# PIC_backpack.net
KiCad netlist of a schematic drawn in EAGLE
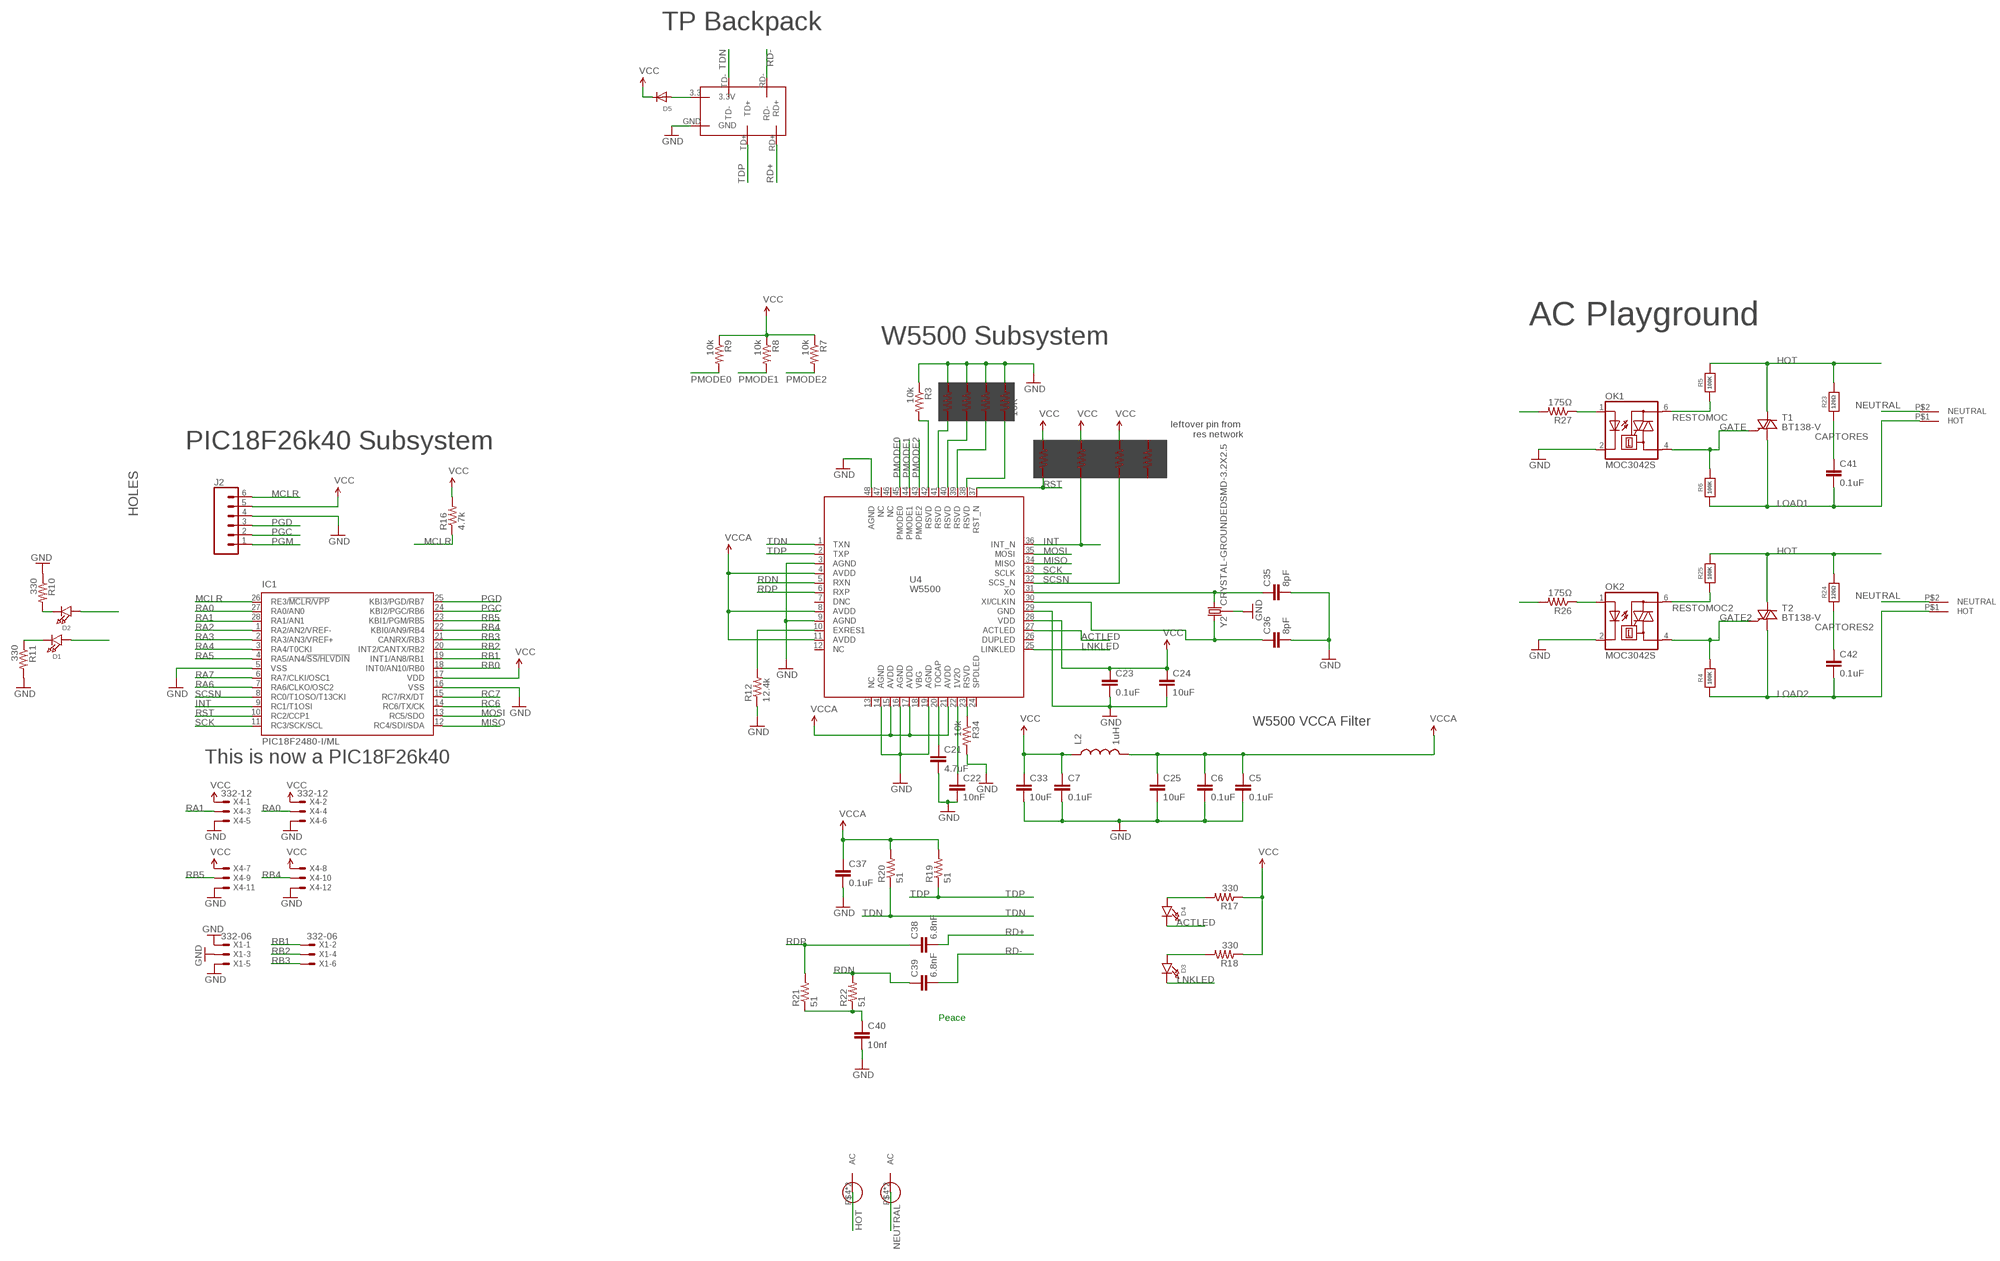
[diagram p0: schematic, sheet 1]

(export (version "E")
  (design (tool "Eeschema 10.0.6"))
  (components
    (comp (ref "C5")
      (value "0.1uF")
      (footprint "eagle-import:0603-CAP")
      (libsource (lib "eagle-import") (part "SparkFun-Passives_CAP0603-CAP"))
    )
    (comp (ref "C6")
      (value "0.1uF")
      (footprint "eagle-import:0603-CAP")
      (libsource (lib "eagle-import") (part "SparkFun-Passives_CAP0603-CAP"))
    )
    (comp (ref "C7")
      (value "0.1uF")
      (footprint "eagle-import:0603-CAP")
      (libsource (lib "eagle-import") (part "SparkFun-Passives_CAP0603-CAP"))
    )
    (comp (ref "C21")
      (value "4.7uF")
      (footprint "eagle-import:0603-CAP")
      (libsource (lib "eagle-import") (part "SparkFun-Passives_CAP0603-CAP"))
    )
    (comp (ref "C22")
      (value "10nF")
      (footprint "eagle-import:0603-CAP")
      (libsource (lib "eagle-import") (part "SparkFun-Passives_CAP0603-CAP"))
    )
    (comp (ref "C23")
      (value "0.1uF")
      (footprint "eagle-import:0603-CAP")
      (libsource (lib "eagle-import") (part "SparkFun-Passives_CAP0603-CAP"))
    )
    (comp (ref "C24")
      (value "10uF")
      (footprint "eagle-import:0603-CAP")
      (libsource (lib "eagle-import") (part "SparkFun-Passives_CAP0603-CAP"))
    )
    (comp (ref "C25")
      (value "10uF")
      (footprint "eagle-import:0603-CAP")
      (libsource (lib "eagle-import") (part "SparkFun-Passives_CAP0603-CAP"))
    )
    (comp (ref "C33")
      (value "10uF")
      (footprint "eagle-import:0603-CAP")
      (libsource (lib "eagle-import") (part "SparkFun-Passives_CAP0603-CAP"))
    )
    (comp (ref "C35")
      (value "8pF")
      (footprint "eagle-import:0603-CAP")
      (libsource (lib "eagle-import") (part "SparkFun-Passives_CAP0603-CAP"))
    )
    (comp (ref "C36")
      (value "8pF")
      (footprint "eagle-import:0603-CAP")
      (libsource (lib "eagle-import") (part "SparkFun-Passives_CAP0603-CAP"))
    )
    (comp (ref "C37")
      (value "0.1uF")
      (footprint "eagle-import:0603-CAP")
      (libsource (lib "eagle-import") (part "SparkFun-Passives_CAP0603-CAP"))
    )
    (comp (ref "C38")
      (value "6.8nF")
      (footprint "eagle-import:0603-CAP")
      (libsource (lib "eagle-import") (part "SparkFun-Passives_CAP0603-CAP"))
    )
    (comp (ref "C39")
      (value "6.8nF")
      (footprint "eagle-import:0603-CAP")
      (libsource (lib "eagle-import") (part "SparkFun-Passives_CAP0603-CAP"))
    )
    (comp (ref "C40")
      (value "10nf")
      (footprint "eagle-import:0603-CAP")
      (libsource (lib "eagle-import") (part "SparkFun-Passives_CAP0603-CAP"))
    )
    (comp (ref "C41")
      (value "0.1uF")
      (footprint "eagle-import:1210")
      (libsource (lib "eagle-import") (part "CAP1210"))
    )
    (comp (ref "C42")
      (value "0.1uF")
      (footprint "eagle-import:1210")
      (libsource (lib "eagle-import") (part "CAP1210"))
    )
    (comp (ref "D1")
      (value "LED0603_NOOUTLINE")
      (footprint "eagle-import:CHIPLED_0603_NOOUTLINE")
      (libsource (lib "eagle-import") (part "LED0603_NOOUTLINE"))
    )
    (comp (ref "D2")
      (value "LED0603_NOOUTLINE")
      (footprint "eagle-import:CHIPLED_0603_NOOUTLINE")
      (libsource (lib "eagle-import") (part "LED0603_NOOUTLINE"))
    )
    (comp (ref "D3")
      (value "LED0603_NOOUTLINE")
      (footprint "eagle-import:CHIPLED_0603_NOOUTLINE")
      (libsource (lib "eagle-import") (part "LED0603_NOOUTLINE"))
    )
    (comp (ref "D4")
      (value "LED0603_NOOUTLINE")
      (footprint "eagle-import:CHIPLED_0603_NOOUTLINE")
      (libsource (lib "eagle-import") (part "LED0603_NOOUTLINE"))
    )
    (comp (ref "D5")
      (value "DIODESOD-123")
      (footprint "eagle-import:SOD-123")
      (libsource (lib "eagle-import") (part "DIODESOD-123"))
    )
    (comp (ref "IC1")
      (value "PIC18F2480-I/ML")
      (footprint "eagle-import:QFN28-ML_6X6MM")
      (fields (field (name "MF") "MICROCHIP"))
      (libsource (lib "eagle-import") (part "PIC18F280-I/ML4"))
    )
    (comp (ref "J2")
      (value "CONN_06NO_SILK_FEMALE_PTH")
      (footprint "eagle-import:1X06_NO_SILK")
      (libsource (lib "eagle-import") (part "CONN_06NO_SILK_FEMALE_PTH"))
    )
    (comp (ref "L2")
      (value "1uH")
      (footprint "eagle-import:0603")
      (libsource (lib "eagle-import") (part "INDUCTOR0603"))
    )
    (comp (ref "OK1")
      (value "MOC3042S")
      (footprint "eagle-import:DIL6-SMD")
      (fields (field (name "MF") "FAIRCHILD SEMICONDUCTOR") (field (name "MPN") "MOC3042SM"))
      (libsource (lib "eagle-import") (part "MOC30S42"))
    )
    (comp (ref "OK2")
      (value "MOC3042S")
      (footprint "eagle-import:DIL6-SMD")
      (fields (field (name "MF") "FAIRCHILD SEMICONDUCTOR") (field (name "MPN") "MOC3042SM"))
      (libsource (lib "eagle-import") (part "MOC30S42"))
    )
    (comp (ref "R1")
      (value "10K")
      (footprint "eagle-import:RESPACK_4X0603")
      (libsource (lib "eagle-import") (part "RESISTOR_4PACK_US"))
    )
    (comp (ref "R2")
      (value "10K")
      (footprint "eagle-import:RESPACK_4X0603")
      (libsource (lib "eagle-import") (part "RESISTOR_4PACK_US"))
    )
    (comp (ref "R3")
      (value "10k")
      (footprint "eagle-import:0603-RES")
      (libsource (lib "eagle-import") (part "RESISTOR0603-RES"))
    )
    (comp (ref "R4")
      (value "100K")
      (footprint "eagle-import:0805_10MGAP")
      (libsource (lib "eagle-import") (part "RESISTOR0805_10MGAP"))
    )
    (comp (ref "R5")
      (value "100K")
      (footprint "eagle-import:0805_10MGAP")
      (libsource (lib "eagle-import") (part "RESISTOR0805_10MGAP"))
    )
    (comp (ref "R6")
      (value "100K")
      (footprint "eagle-import:0805_10MGAP")
      (libsource (lib "eagle-import") (part "RESISTOR0805_10MGAP"))
    )
    (comp (ref "R7")
      (value "10k")
      (footprint "eagle-import:0603-RES")
      (libsource (lib "eagle-import") (part "RESISTOR0603-RES"))
    )
    (comp (ref "R8")
      (value "10k")
      (footprint "eagle-import:0603-RES")
      (libsource (lib "eagle-import") (part "RESISTOR0603-RES"))
    )
    (comp (ref "R9")
      (value "10k")
      (footprint "eagle-import:0603-RES")
      (libsource (lib "eagle-import") (part "RESISTOR0603-RES"))
    )
    (comp (ref "R10")
      (value "330")
      (footprint "eagle-import:0603-RES")
      (libsource (lib "eagle-import") (part "RESISTOR0603-RES"))
    )
    (comp (ref "R11")
      (value "330")
      (footprint "eagle-import:0603-RES")
      (libsource (lib "eagle-import") (part "RESISTOR0603-RES"))
    )
    (comp (ref "R12")
      (value "12.4k")
      (footprint "eagle-import:0603-RES")
      (libsource (lib "eagle-import") (part "RESISTOR0603-RES"))
    )
    (comp (ref "R16")
      (value "4.7k")
      (footprint "eagle-import:0603-RES")
      (libsource (lib "eagle-import") (part "RESISTOR0603-RES"))
    )
    (comp (ref "R17")
      (value "330")
      (footprint "eagle-import:0603-RES")
      (libsource (lib "eagle-import") (part "RESISTOR0603-RES"))
    )
    (comp (ref "R18")
      (value "330")
      (footprint "eagle-import:0603-RES")
      (libsource (lib "eagle-import") (part "RESISTOR0603-RES"))
    )
    (comp (ref "R19")
      (value "51")
      (footprint "eagle-import:0603-RES")
      (libsource (lib "eagle-import") (part "RESISTOR0603-RES"))
    )
    (comp (ref "R20")
      (value "51")
      (footprint "eagle-import:0603-RES")
      (libsource (lib "eagle-import") (part "RESISTOR0603-RES"))
    )
    (comp (ref "R21")
      (value "51")
      (footprint "eagle-import:0603-RES")
      (libsource (lib "eagle-import") (part "RESISTOR0603-RES"))
    )
    (comp (ref "R22")
      (value "51")
      (footprint "eagle-import:0603-RES")
      (libsource (lib "eagle-import") (part "RESISTOR0603-RES"))
    )
    (comp (ref "R23")
      (value "120Ω")
      (footprint "eagle-import:0805_10MGAP")
      (libsource (lib "eagle-import") (part "RESISTOR0805_10MGAP"))
    )
    (comp (ref "R24")
      (value "120Ω")
      (footprint "eagle-import:0805_10MGAP")
      (libsource (lib "eagle-import") (part "RESISTOR0805_10MGAP"))
    )
    (comp (ref "R25")
      (value "100K")
      (footprint "eagle-import:0805_10MGAP")
      (libsource (lib "eagle-import") (part "RESISTOR0805_10MGAP"))
    )
    (comp (ref "R26")
      (value "175Ω")
      (footprint "eagle-import:0603-RES")
      (libsource (lib "eagle-import") (part "RESISTOR0603-RES"))
    )
    (comp (ref "R27")
      (value "175Ω")
      (footprint "eagle-import:0603-RES")
      (libsource (lib "eagle-import") (part "RESISTOR0603-RES"))
    )
    (comp (ref "R34")
      (value "10k")
      (footprint "eagle-import:0603-RES")
      (libsource (lib "eagle-import") (part "RESISTOR0603-RES"))
    )
    (comp (ref "T1")
      (value "BT138-V")
      (footprint "eagle-import:TO220BV")
      (libsource (lib "eagle-import") (part "BT138-V"))
    )
    (comp (ref "T2")
      (value "BT138-V")
      (footprint "eagle-import:TO220BV")
      (libsource (lib "eagle-import") (part "BT138-V"))
    )
    (comp (ref "U$1")
      (value "TPLINK_BACKPACK")
      (footprint "eagle-import:BACKPACK_WITH_PROTO")
      (libsource (lib "eagle-import") (part "TPLINK_BACKPACK"))
    )
    (comp (ref "U$2")
      (value "AC_BLADE")
      (footprint "eagle-import:AC_BLADE")
      (libsource (lib "eagle-import") (part "AC_BLADE"))
    )
    (comp (ref "U$3")
      (value "AC_BLADE")
      (footprint "eagle-import:AC_BLADE")
      (libsource (lib "eagle-import") (part "AC_BLADE"))
    )
    (comp (ref "U$4")
      (value "AC_TERMINAL")
      (footprint "eagle-import:AC_TERMINAL")
      (libsource (lib "eagle-import") (part "AC_TERMINAL"))
    )
    (comp (ref "U$5")
      (value "AC_TERMINAL")
      (footprint "eagle-import:AC_TERMINAL")
      (libsource (lib "eagle-import") (part "AC_TERMINAL"))
    )
    (comp (ref "U4")
      (value "W5500")
      (footprint "eagle-import:W5500")
      (libsource (lib "eagle-import") (part "W5500"))
    )
    (comp (ref "X1")
      (value "332-06")
      (footprint "eagle-import:332-06")
      (libsource (lib "eagle-import") (part "332-06"))
    )
    (comp (ref "X4")
      (value "332-12")
      (footprint "eagle-import:332-12")
      (libsource (lib "eagle-import") (part "332-12"))
    )
    (comp (ref "Y2")
      (value "CRYSTAL-GROUNDEDSMD-3.2X2.5")
      (footprint "eagle-import:CRYSTAL-SMD-3.2X2.5MM")
      (libsource (lib "eagle-import") (part "CRYSTAL-GROUNDEDSMD-3.2X2.5"))
    )
  )
  (nets
    (net (code "1") (name "/ACTLED") (class "Default")
      (node (ref "D4") (pin "C") (pinfunction "C_C") (pintype "passive"))
      (node (ref "U4") (pin "27") (pinfunction "ACTLED_27") (pintype "passive"))
    )
    (net (code "2") (name "/CAPTORES") (class "Default")
      (node (ref "C41") (pin "1") (pinfunction "1_1") (pintype "passive"))
      (node (ref "R23") (pin "1") (pinfunction "1_1") (pintype "passive"))
    )
    (net (code "3") (name "/CAPTORES2") (class "Default")
      (node (ref "C42") (pin "1") (pinfunction "1_1") (pintype "passive"))
      (node (ref "R24") (pin "1") (pinfunction "1_1") (pintype "passive"))
    )
    (net (code "4") (name "/GATE") (class "Default")
      (node (ref "OK1") (pin "4") (pinfunction "A1_4") (pintype "passive"))
      (node (ref "R6") (pin "2") (pinfunction "2_2") (pintype "passive"))
      (node (ref "T1") (pin "G") (pinfunction "G_G") (pintype "passive"))
    )
    (net (code "5") (name "/GATE2") (class "Default")
      (node (ref "OK2") (pin "4") (pinfunction "A1_4") (pintype "passive"))
      (node (ref "R4") (pin "2") (pinfunction "2_2") (pintype "passive"))
      (node (ref "T2") (pin "G") (pinfunction "G_G") (pintype "passive"))
    )
    (net (code "6") (name "/HOT") (class "Default")
      (node (ref "R23") (pin "2") (pinfunction "2_2") (pintype "passive"))
      (node (ref "R24") (pin "2") (pinfunction "2_2") (pintype "passive"))
      (node (ref "R25") (pin "2") (pinfunction "2_2") (pintype "passive"))
      (node (ref "R5") (pin "2") (pinfunction "2_2") (pintype "passive"))
      (node (ref "T1") (pin "T2") (pinfunction "A2_T2") (pintype "passive"))
      (node (ref "T2") (pin "T2") (pinfunction "A2_T2") (pintype "passive"))
      (node (ref "U$2") (pin "P$4") (pinfunction "AC_P$4") (pintype "bidirectional"))
      (node (ref "U$2") (pin "P$5") (pinfunction "AC_P$5") (pintype "bidirectional"))
    )
    (net (code "7") (name "/INT") (class "Default")
      (node (ref "IC1") (pin "9") (pinfunction "RC1/T1OSI_9") (pintype "bidirectional"))
      (node (ref "R2") (pin "3") (pinfunction "1_3") (pintype "passive"))
      (node (ref "U4") (pin "36") (pinfunction "INT_N_36") (pintype "passive"))
    )
    (net (code "8") (name "/LNKLED") (class "Default")
      (node (ref "D3") (pin "C") (pinfunction "C_C") (pintype "passive"))
      (node (ref "U4") (pin "25") (pinfunction "LINKLED_25") (pintype "passive"))
    )
    (net (code "9") (name "/LOAD1") (class "Default")
      (node (ref "C41") (pin "2") (pinfunction "2_2") (pintype "passive"))
      (node (ref "R6") (pin "1") (pinfunction "1_1") (pintype "passive"))
      (node (ref "T1") (pin "T1") (pinfunction "A1_T1") (pintype "passive"))
      (node (ref "U$5") (pin "P$1") (pinfunction "HOT_P$1") (pintype "bidirectional"))
    )
    (net (code "10") (name "/LOAD2") (class "Default")
      (node (ref "C42") (pin "2") (pinfunction "2_2") (pintype "passive"))
      (node (ref "R4") (pin "1") (pinfunction "1_1") (pintype "passive"))
      (node (ref "T2") (pin "T1") (pinfunction "A1_T1") (pintype "passive"))
      (node (ref "U$4") (pin "P$1") (pinfunction "HOT_P$1") (pintype "bidirectional"))
    )
    (net (code "11") (name "/MCLR") (class "Default")
      (node (ref "IC1") (pin "26") (pinfunction "RE3/~{MCLR/VPP}_26") (pintype "input"))
      (node (ref "J2") (pin "6") (pinfunction "6_6") (pintype "passive"))
      (node (ref "R16") (pin "1") (pinfunction "1_1") (pintype "passive"))
    )
    (net (code "12") (name "/MISO") (class "Default")
      (node (ref "IC1") (pin "12") (pinfunction "RC4/SDI/SDA_12") (pintype "bidirectional"))
      (node (ref "U4") (pin "34") (pinfunction "MISO_34") (pintype "passive"))
    )
    (net (code "13") (name "/MOSI") (class "Default")
      (node (ref "IC1") (pin "13") (pinfunction "RC5/SDO_13") (pintype "bidirectional"))
      (node (ref "U4") (pin "35") (pinfunction "MOSI_35") (pintype "passive"))
    )
    (net (code "14") (name "/NEUTRAL") (class "Default")
      (node (ref "U$3") (pin "P$4") (pinfunction "AC_P$4") (pintype "bidirectional"))
      (node (ref "U$3") (pin "P$5") (pinfunction "AC_P$5") (pintype "bidirectional"))
      (node (ref "U$4") (pin "P$2") (pinfunction "NEUTRAL_P$2") (pintype "bidirectional"))
      (node (ref "U$5") (pin "P$2") (pinfunction "NEUTRAL_P$2") (pintype "bidirectional"))
    )
    (net (code "15") (name "/PGC") (class "Default")
      (node (ref "IC1") (pin "24") (pinfunction "KBI2/PGC/RB6_24") (pintype "bidirectional"))
      (node (ref "J2") (pin "2") (pinfunction "2_2") (pintype "passive"))
    )
    (net (code "16") (name "/PGD") (class "Default")
      (node (ref "IC1") (pin "25") (pinfunction "KBI3/PGD/RB7_25") (pintype "bidirectional"))
      (node (ref "J2") (pin "3") (pinfunction "3_3") (pintype "passive"))
    )
    (net (code "17") (name "/PGM") (class "Default")
      (node (ref "J2") (pin "1") (pinfunction "1_1") (pintype "passive"))
    )
    (net (code "18") (name "/PMODE0") (class "Default")
      (node (ref "R9") (pin "2") (pinfunction "2_2") (pintype "passive"))
      (node (ref "U4") (pin "45") (pinfunction "PMODE0_45") (pintype "passive"))
    )
    (net (code "19") (name "/PMODE1") (class "Default")
      (node (ref "R8") (pin "2") (pinfunction "2_2") (pintype "passive"))
      (node (ref "U4") (pin "44") (pinfunction "PMODE1_44") (pintype "passive"))
    )
    (net (code "20") (name "/PMODE2") (class "Default")
      (node (ref "R7") (pin "2") (pinfunction "2_2") (pintype "passive"))
      (node (ref "U4") (pin "43") (pinfunction "PMODE2_43") (pintype "passive"))
    )
    (net (code "21") (name "/RA0") (class "Default")
      (node (ref "IC1") (pin "27") (pinfunction "RA0/AN0_27") (pintype "bidirectional"))
      (node (ref "X4") (pin "4") (pinfunction "S_4") (pintype "passive"))
    )
    (net (code "22") (name "/RA1") (class "Default")
      (node (ref "IC1") (pin "28") (pinfunction "RA1/AN1_28") (pintype "bidirectional"))
      (node (ref "X4") (pin "3") (pinfunction "S_3") (pintype "passive"))
    )
    (net (code "23") (name "/RA2") (class "Default")
      (node (ref "IC1") (pin "1") (pinfunction "RA2/AN2/VREF-_1") (pintype "bidirectional"))
    )
    (net (code "24") (name "/RA3") (class "Default")
      (node (ref "IC1") (pin "2") (pinfunction "RA3/AN3/VREF+_2") (pintype "bidirectional"))
    )
    (net (code "25") (name "/RA4") (class "Default")
      (node (ref "IC1") (pin "3") (pinfunction "RA4/T0CKI_3") (pintype "bidirectional"))
      (node (ref "R26") (pin "2") (pinfunction "2_2") (pintype "passive"))
    )
    (net (code "26") (name "/RA5") (class "Default")
      (node (ref "IC1") (pin "4") (pinfunction "RA5/AN4/~{SS/HLVDIN}_4") (pintype "bidirectional"))
      (node (ref "R27") (pin "2") (pinfunction "2_2") (pintype "passive"))
    )
    (net (code "27") (name "/RA6") (class "Default")
      (node (ref "IC1") (pin "7") (pinfunction "RA6/CLKO/OSC2_7") (pintype "output"))
    )
    (net (code "28") (name "/RA7") (class "Default")
      (node (ref "IC1") (pin "6") (pinfunction "RA7/CLKI/OSC1_6") (pintype "input"))
    )
    (net (code "29") (name "/RB0") (class "Default")
      (node (ref "IC1") (pin "18") (pinfunction "INT0/AN10/RB0_18") (pintype "bidirectional"))
    )
    (net (code "30") (name "/RB1") (class "Default")
      (node (ref "IC1") (pin "19") (pinfunction "INT1/AN8/RB1_19") (pintype "bidirectional"))
      (node (ref "X1") (pin "2") (pinfunction "S_2") (pintype "passive"))
    )
    (net (code "31") (name "/RB2") (class "Default")
      (node (ref "IC1") (pin "20") (pinfunction "INT2/CANTX/RB2_20") (pintype "bidirectional"))
      (node (ref "X1") (pin "4") (pinfunction "S_4") (pintype "passive"))
    )
    (net (code "32") (name "/RB3") (class "Default")
      (node (ref "IC1") (pin "21") (pinfunction "CANRX/RB3_21") (pintype "bidirectional"))
      (node (ref "X1") (pin "6") (pinfunction "S_6") (pintype "passive"))
    )
    (net (code "33") (name "/RB4") (class "Default")
      (node (ref "IC1") (pin "22") (pinfunction "KBI0/AN9/RB4_22") (pintype "bidirectional"))
      (node (ref "X4") (pin "10") (pinfunction "S_10") (pintype "passive"))
    )
    (net (code "34") (name "/RB5") (class "Default")
      (node (ref "IC1") (pin "23") (pinfunction "KBI1/PGM/RB5_23") (pintype "bidirectional"))
      (node (ref "X4") (pin "9") (pinfunction "S_9") (pintype "passive"))
    )
    (net (code "35") (name "/RC6") (class "Default")
      (node (ref "D2") (pin "A") (pinfunction "A_A") (pintype "passive"))
      (node (ref "IC1") (pin "14") (pinfunction "RC6/TX/CK_14") (pintype "bidirectional"))
    )
    (net (code "36") (name "/RC7") (class "Default")
      (node (ref "D1") (pin "A") (pinfunction "A_A") (pintype "passive"))
      (node (ref "IC1") (pin "15") (pinfunction "RC7/RX/DT_15") (pintype "bidirectional"))
    )
    (net (code "37") (name "/RD+") (class "Default")
      (node (ref "C38") (pin "2") (pinfunction "2_2") (pintype "passive"))
      (node (ref "U$1") (pin "RD+") (pinfunction "RD+_RD+") (pintype "bidirectional"))
    )
    (net (code "38") (name "/RD-") (class "Default")
      (node (ref "C39") (pin "2") (pinfunction "2_2") (pintype "passive"))
      (node (ref "U$1") (pin "RD-") (pinfunction "RD-_RD-") (pintype "bidirectional"))
    )
    (net (code "39") (name "/RDN") (class "Default")
      (node (ref "C39") (pin "1") (pinfunction "1_1") (pintype "passive"))
      (node (ref "R22") (pin "2") (pinfunction "2_2") (pintype "passive"))
      (node (ref "U4") (pin "5") (pinfunction "RXN_5") (pintype "passive"))
    )
    (net (code "40") (name "/RDP") (class "Default")
      (node (ref "C38") (pin "1") (pinfunction "1_1") (pintype "passive"))
      (node (ref "R21") (pin "2") (pinfunction "2_2") (pintype "passive"))
      (node (ref "U4") (pin "6") (pinfunction "RXP_6") (pintype "passive"))
    )
    (net (code "41") (name "/RESTOMOC") (class "Default")
      (node (ref "OK1") (pin "6") (pinfunction "A2_6") (pintype "passive"))
      (node (ref "R5") (pin "1") (pinfunction "1_1") (pintype "passive"))
    )
    (net (code "42") (name "/RESTOMOC2") (class "Default")
      (node (ref "OK2") (pin "6") (pinfunction "A2_6") (pintype "passive"))
      (node (ref "R25") (pin "1") (pinfunction "1_1") (pintype "passive"))
    )
    (net (code "43") (name "/RST") (class "Default")
      (node (ref "IC1") (pin "10") (pinfunction "RC2/CCP1_10") (pintype "bidirectional"))
      (node (ref "R2") (pin "2") (pinfunction "1_2") (pintype "passive"))
      (node (ref "U4") (pin "37") (pinfunction "RST_N_37") (pintype "passive"))
    )
    (net (code "44") (name "/SCK") (class "Default")
      (node (ref "IC1") (pin "11") (pinfunction "RC3/SCK/SCL_11") (pintype "bidirectional"))
      (node (ref "U4") (pin "33") (pinfunction "SCLK_33") (pintype "passive"))
    )
    (net (code "45") (name "/SCSN") (class "Default")
      (node (ref "IC1") (pin "8") (pinfunction "RC0/T1OSO/T13CKI_8") (pintype "bidirectional"))
      (node (ref "R2") (pin "4") (pinfunction "1_4") (pintype "passive"))
      (node (ref "U4") (pin "32") (pinfunction "SCS_N_32") (pintype "passive"))
    )
    (net (code "46") (name "/TDN") (class "Default")
      (node (ref "R20") (pin "1") (pinfunction "1_1") (pintype "passive"))
      (node (ref "U$1") (pin "TD-") (pinfunction "TD-_TD-") (pintype "bidirectional"))
      (node (ref "U4") (pin "1") (pinfunction "TXN_1") (pintype "passive"))
    )
    (net (code "47") (name "/TDP") (class "Default")
      (node (ref "R19") (pin "1") (pinfunction "1_1") (pintype "passive"))
      (node (ref "U$1") (pin "TD+") (pinfunction "TD+_TD+") (pintype "bidirectional"))
      (node (ref "U4") (pin "2") (pinfunction "TXP_2") (pintype "passive"))
    )
    (net (code "48") (name "GND") (class "Default")
      (node (ref "C21") (pin "2") (pinfunction "2_2") (pintype "passive"))
      (node (ref "C22") (pin "2") (pinfunction "2_2") (pintype "passive"))
      (node (ref "C23") (pin "2") (pinfunction "2_2") (pintype "passive"))
      (node (ref "C24") (pin "2") (pinfunction "2_2") (pintype "passive"))
      (node (ref "C25") (pin "2") (pinfunction "2_2") (pintype "passive"))
      (node (ref "C33") (pin "2") (pinfunction "2_2") (pintype "passive"))
      (node (ref "C35") (pin "2") (pinfunction "2_2") (pintype "passive"))
      (node (ref "C36") (pin "2") (pinfunction "2_2") (pintype "passive"))
      (node (ref "C37") (pin "2") (pinfunction "2_2") (pintype "passive"))
      (node (ref "C40") (pin "2") (pinfunction "2_2") (pintype "passive"))
      (node (ref "C5") (pin "2") (pinfunction "2_2") (pintype "passive"))
      (node (ref "C6") (pin "2") (pinfunction "2_2") (pintype "passive"))
      (node (ref "C7") (pin "2") (pinfunction "2_2") (pintype "passive"))
      (node (ref "IC1") (pin "16") (pinfunction "VSS_16") (pintype "power_in"))
      (node (ref "IC1") (pin "5") (pinfunction "VSS_5") (pintype "power_in"))
      (node (ref "J2") (pin "4") (pinfunction "4_4") (pintype "passive"))
      (node (ref "OK1") (pin "2") (pinfunction "C_2") (pintype "passive"))
      (node (ref "OK2") (pin "2") (pinfunction "C_2") (pintype "passive"))
      (node (ref "R1") (pin "5") (pinfunction "2_5") (pintype "passive"))
      (node (ref "R1") (pin "6") (pinfunction "2_6") (pintype "passive"))
      (node (ref "R1") (pin "7") (pinfunction "2_7") (pintype "passive"))
      (node (ref "R1") (pin "8") (pinfunction "2_8") (pintype "passive"))
      (node (ref "R10") (pin "1") (pinfunction "1_1") (pintype "passive"))
      (node (ref "R11") (pin "2") (pinfunction "2_2") (pintype "passive"))
      (node (ref "R12") (pin "1") (pinfunction "1_1") (pintype "passive"))
      (node (ref "R3") (pin "1") (pinfunction "1_1") (pintype "passive"))
      (node (ref "R34") (pin "2") (pinfunction "2_2") (pintype "passive"))
      (node (ref "U$1") (pin "GND") (pinfunction "GND_GND") (pintype "bidirectional"))
      (node (ref "U4") (pin "14") (pinfunction "AGND_14") (pintype "passive"))
      (node (ref "U4") (pin "16") (pinfunction "AGND_16") (pintype "passive"))
      (node (ref "U4") (pin "19") (pinfunction "AGND_19") (pintype "passive"))
      (node (ref "U4") (pin "29") (pinfunction "GND_29") (pintype "passive"))
      (node (ref "U4") (pin "3") (pinfunction "AGND_3") (pintype "passive"))
      (node (ref "U4") (pin "48") (pinfunction "AGND_48") (pintype "passive"))
      (node (ref "U4") (pin "9") (pinfunction "AGND_9") (pintype "passive"))
      (node (ref "X1") (pin "1") (pinfunction "S_1") (pintype "passive"))
      (node (ref "X1") (pin "3") (pinfunction "S_3") (pintype "passive"))
      (node (ref "X1") (pin "5") (pinfunction "S_5") (pintype "passive"))
      (node (ref "X4") (pin "11") (pinfunction "S_11") (pintype "passive"))
      (node (ref "X4") (pin "12") (pinfunction "S_12") (pintype "passive"))
      (node (ref "X4") (pin "5") (pinfunction "S_5") (pintype "passive"))
      (node (ref "X4") (pin "6") (pinfunction "S_6") (pintype "passive"))
      (node (ref "Y2") (pin "2") (pinfunction "3_2") (pintype "passive"))
      (node (ref "Y2") (pin "4") (pinfunction "3_4") (pintype "passive"))
    )
    (net (code "49") (name "Net-(C40-Pad1)") (class "Default")
      (node (ref "C40") (pin "1") (pinfunction "1_1") (pintype "passive"))
      (node (ref "R21") (pin "1") (pinfunction "1_1") (pintype "passive"))
      (node (ref "R22") (pin "1") (pinfunction "1_1") (pintype "passive"))
    )
    (net (code "50") (name "Net-(D1-PadC)") (class "Default")
      (node (ref "D1") (pin "C") (pinfunction "C_C") (pintype "passive"))
      (node (ref "R11") (pin "1") (pinfunction "1_1") (pintype "passive"))
    )
    (net (code "51") (name "Net-(D2-PadC)") (class "Default")
      (node (ref "D2") (pin "C") (pinfunction "C_C") (pintype "passive"))
      (node (ref "R10") (pin "2") (pinfunction "2_2") (pintype "passive"))
    )
    (net (code "52") (name "Net-(D3-PadA)") (class "Default")
      (node (ref "D3") (pin "A") (pinfunction "A_A") (pintype "passive"))
      (node (ref "R18") (pin "2") (pinfunction "2_2") (pintype "passive"))
    )
    (net (code "53") (name "Net-(D4-PadA)") (class "Default")
      (node (ref "D4") (pin "A") (pinfunction "A_A") (pintype "passive"))
      (node (ref "R17") (pin "2") (pinfunction "2_2") (pintype "passive"))
    )
    (net (code "54") (name "Net-(OK1-A)") (class "Default")
      (node (ref "OK1") (pin "1") (pinfunction "A_1") (pintype "passive"))
      (node (ref "R27") (pin "1") (pinfunction "1_1") (pintype "passive"))
    )
    (net (code "55") (name "Net-(OK2-A)") (class "Default")
      (node (ref "OK2") (pin "1") (pinfunction "A_1") (pintype "passive"))
      (node (ref "R26") (pin "1") (pinfunction "1_1") (pintype "passive"))
    )
    (net (code "56") (name "Net-(R1-Pad1)") (class "Default")
      (node (ref "R1") (pin "1") (pinfunction "1_1") (pintype "passive"))
      (node (ref "U4") (pin "41") (pinfunction "RSVD_41") (pintype "passive"))
    )
    (net (code "57") (name "Net-(R1B-1)") (class "Default")
      (node (ref "R1") (pin "2") (pinfunction "1_2") (pintype "passive"))
      (node (ref "U4") (pin "40") (pinfunction "RSVD_40") (pintype "passive"))
    )
    (net (code "58") (name "Net-(R1C-1)") (class "Default")
      (node (ref "R1") (pin "3") (pinfunction "1_3") (pintype "passive"))
      (node (ref "U4") (pin "39") (pinfunction "RSVD_39") (pintype "passive"))
    )
    (net (code "59") (name "Net-(R1D-1)") (class "Default")
      (node (ref "R1") (pin "4") (pinfunction "1_4") (pintype "passive"))
      (node (ref "U4") (pin "38") (pinfunction "RSVD_38") (pintype "passive"))
    )
    (net (code "60") (name "Net-(R3-Pad2)") (class "Default")
      (node (ref "R3") (pin "2") (pinfunction "2_2") (pintype "passive"))
      (node (ref "U4") (pin "42") (pinfunction "RSVD_42") (pintype "passive"))
    )
    (net (code "61") (name "Net-(R34-Pad1)") (class "Default")
      (node (ref "R34") (pin "1") (pinfunction "1_1") (pintype "passive"))
      (node (ref "U4") (pin "23") (pinfunction "RSVD_23") (pintype "passive"))
    )
    (net (code "62") (name "Net-(U$1-3.3V)") (class "Default")
      (node (ref "D5") (pin "A") (pinfunction "A_A") (pintype "passive"))
      (node (ref "U$1") (pin "3.3") (pinfunction "3.3V_3.3") (pintype "bidirectional"))
    )
    (net (code "63") (name "Net-(U4-1V2O)") (class "Default")
      (node (ref "C22") (pin "1") (pinfunction "1_1") (pintype "passive"))
      (node (ref "U4") (pin "22") (pinfunction "1V2O_22") (pintype "passive"))
    )
    (net (code "64") (name "Net-(U4-EXRES1)") (class "Default")
      (node (ref "R12") (pin "2") (pinfunction "2_2") (pintype "passive"))
      (node (ref "U4") (pin "10") (pinfunction "EXRES1_10") (pintype "passive"))
    )
    (net (code "65") (name "Net-(U4-TOCAP)") (class "Default")
      (node (ref "C21") (pin "1") (pinfunction "1_1") (pintype "passive"))
      (node (ref "U4") (pin "20") (pinfunction "TOCAP_20") (pintype "passive"))
    )
    (net (code "66") (name "Net-(U4-XI{slash}CLKIN)") (class "Default")
      (node (ref "C36") (pin "1") (pinfunction "1_1") (pintype "passive"))
      (node (ref "U4") (pin "30") (pinfunction "XI/CLKIN_30") (pintype "passive"))
      (node (ref "Y2") (pin "1") (pinfunction "1_1") (pintype "passive"))
    )
    (net (code "67") (name "Net-(U4-XO)") (class "Default")
      (node (ref "C35") (pin "1") (pinfunction "1_1") (pintype "passive"))
      (node (ref "U4") (pin "31") (pinfunction "XO_31") (pintype "passive"))
      (node (ref "Y2") (pin "3") (pinfunction "2_3") (pintype "passive"))
    )
    (net (code "68") (name "VCC") (class "Default")
      (node (ref "C23") (pin "1") (pinfunction "1_1") (pintype "passive"))
      (node (ref "C24") (pin "1") (pinfunction "1_1") (pintype "passive"))
      (node (ref "C33") (pin "1") (pinfunction "1_1") (pintype "passive"))
      (node (ref "C7") (pin "1") (pinfunction "1_1") (pintype "passive"))
      (node (ref "D5") (pin "C") (pinfunction "C_C") (pintype "passive"))
      (node (ref "IC1") (pin "17") (pinfunction "VDD_17") (pintype "power_in"))
      (node (ref "J2") (pin "5") (pinfunction "5_5") (pintype "passive"))
      (node (ref "L2") (pin "1") (pinfunction "1_1") (pintype "passive"))
      (node (ref "R16") (pin "2") (pinfunction "2_2") (pintype "passive"))
      (node (ref "R17") (pin "1") (pinfunction "1_1") (pintype "passive"))
      (node (ref "R18") (pin "1") (pinfunction "1_1") (pintype "passive"))
      (node (ref "R2") (pin "5") (pinfunction "2_5") (pintype "passive"))
      (node (ref "R2") (pin "6") (pinfunction "2_6") (pintype "passive"))
      (node (ref "R2") (pin "7") (pinfunction "2_7") (pintype "passive"))
      (node (ref "R7") (pin "1") (pinfunction "1_1") (pintype "passive"))
      (node (ref "R8") (pin "1") (pinfunction "1_1") (pintype "passive"))
      (node (ref "R9") (pin "1") (pinfunction "1_1") (pintype "passive"))
      (node (ref "U4") (pin "28") (pinfunction "VDD_28") (pintype "passive"))
      (node (ref "X4") (pin "1") (pinfunction "S_1") (pintype "passive"))
      (node (ref "X4") (pin "2") (pinfunction "S_2") (pintype "passive"))
      (node (ref "X4") (pin "7") (pinfunction "S_7") (pintype "passive"))
      (node (ref "X4") (pin "8") (pinfunction "S_8") (pintype "passive"))
    )
    (net (code "69") (name "VCCA") (class "Default")
      (node (ref "C25") (pin "1") (pinfunction "1_1") (pintype "passive"))
      (node (ref "C37") (pin "1") (pinfunction "1_1") (pintype "passive"))
      (node (ref "C5") (pin "1") (pinfunction "1_1") (pintype "passive"))
      (node (ref "C6") (pin "1") (pinfunction "1_1") (pintype "passive"))
      (node (ref "L2") (pin "2") (pinfunction "2_2") (pintype "passive"))
      (node (ref "R19") (pin "2") (pinfunction "2_2") (pintype "passive"))
      (node (ref "R20") (pin "2") (pinfunction "2_2") (pintype "passive"))
      (node (ref "U4") (pin "11") (pinfunction "AVDD_11") (pintype "passive"))
      (node (ref "U4") (pin "15") (pinfunction "AVDD_15") (pintype "passive"))
      (node (ref "U4") (pin "17") (pinfunction "AVDD_17") (pintype "passive"))
      (node (ref "U4") (pin "21") (pinfunction "AVDD_21") (pintype "passive"))
      (node (ref "U4") (pin "4") (pinfunction "AVDD_4") (pintype "passive"))
      (node (ref "U4") (pin "8") (pinfunction "AVDD_8") (pintype "passive"))
    )
    (net (code "70") (name "unconnected-(R2-Pad1)") (class "Default")
      (node (ref "R2") (pin "1") (pinfunction "1_1") (pintype "passive"))
    )
    (net (code "71") (name "unconnected-(R2A-2-Pad8)") (class "Default")
      (node (ref "R2") (pin "8") (pinfunction "2_8") (pintype "passive"))
    )
    (net (code "72") (name "unconnected-(U4-DNC-Pad7)") (class "Default")
      (node (ref "U4") (pin "7") (pinfunction "DNC_7") (pintype "passive"))
    )
    (net (code "73") (name "unconnected-(U4-DUPLED-Pad26)") (class "Default")
      (node (ref "U4") (pin "26") (pinfunction "DUPLED_26") (pintype "passive"))
    )
    (net (code "74") (name "unconnected-(U4-NC-Pad12)") (class "Default")
      (node (ref "U4") (pin "12") (pinfunction "NC_12") (pintype "passive"))
    )
    (net (code "75") (name "unconnected-(U4-NC-Pad13)") (class "Default")
      (node (ref "U4") (pin "13") (pinfunction "NC_13") (pintype "passive"))
    )
    (net (code "76") (name "unconnected-(U4-NC-Pad46)") (class "Default")
      (node (ref "U4") (pin "46") (pinfunction "NC_46") (pintype "passive"))
    )
    (net (code "77") (name "unconnected-(U4-NC-Pad47)") (class "Default")
      (node (ref "U4") (pin "47") (pinfunction "NC_47") (pintype "passive"))
    )
    (net (code "78") (name "unconnected-(U4-SPDLED-Pad24)") (class "Default")
      (node (ref "U4") (pin "24") (pinfunction "SPDLED_24") (pintype "passive"))
    )
    (net (code "79") (name "unconnected-(U4-VBG-Pad18)") (class "Default")
      (node (ref "U4") (pin "18") (pinfunction "VBG_18") (pintype "passive"))
    )
  )
)
